# M_E_ext_proto.net
KiCad netlist of a schematic drawn in EAGLE
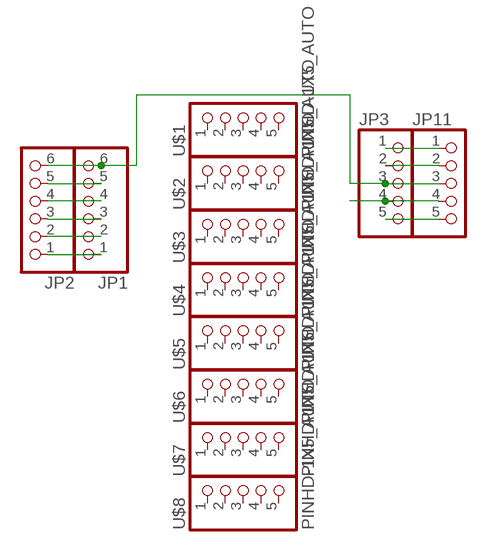
[diagram p0: schematic, sheet 1]

(export (version "E")
  (design (tool "Eeschema 10.0.6"))
  (components
    (comp (ref "JP1")
      (value "PINHD-1X6")
      (footprint "eagle-import:1X06")
      (libsource (lib "eagle-import") (part "PINHD-1X6"))
    )
    (comp (ref "JP2")
      (value "PINHD-1X6")
      (footprint "eagle-import:1X06")
      (libsource (lib "eagle-import") (part "PINHD-1X6"))
    )
    (comp (ref "JP3")
      (value "PINHD-1X5")
      (footprint "eagle-import:1X05")
      (libsource (lib "eagle-import") (part "PINHD-1X5"))
    )
    (comp (ref "JP11")
      (value "PINHD-1X5")
      (footprint "eagle-import:1X05")
      (libsource (lib "eagle-import") (part "PINHD-1X5"))
    )
    (comp (ref "U$1")
      (value "PINHD-1X5_AUTO")
      (footprint "eagle-import:1X5_AUTO")
      (libsource (lib "eagle-import") (part "PINHD-1X5_AUTO"))
    )
    (comp (ref "U$2")
      (value "PINHD-1X5_AUTO")
      (footprint "eagle-import:1X5_AUTO")
      (libsource (lib "eagle-import") (part "PINHD-1X5_AUTO"))
    )
    (comp (ref "U$3")
      (value "PINHD-1X5_AUTO")
      (footprint "eagle-import:1X5_AUTO")
      (libsource (lib "eagle-import") (part "PINHD-1X5_AUTO"))
    )
    (comp (ref "U$4")
      (value "PINHD-1X5_AUTO")
      (footprint "eagle-import:1X5_AUTO")
      (libsource (lib "eagle-import") (part "PINHD-1X5_AUTO"))
    )
    (comp (ref "U$5")
      (value "PINHD-1X5_AUTO")
      (footprint "eagle-import:1X5_AUTO")
      (libsource (lib "eagle-import") (part "PINHD-1X5_AUTO"))
    )
    (comp (ref "U$6")
      (value "PINHD-1X5_AUTO")
      (footprint "eagle-import:1X5_AUTO")
      (libsource (lib "eagle-import") (part "PINHD-1X5_AUTO"))
    )
    (comp (ref "U$7")
      (value "PINHD-1X5_AUTO")
      (footprint "eagle-import:1X5_AUTO")
      (libsource (lib "eagle-import") (part "PINHD-1X5_AUTO"))
    )
    (comp (ref "U$8")
      (value "PINHD-1X5_AUTO")
      (footprint "eagle-import:1X5_AUTO")
      (libsource (lib "eagle-import") (part "PINHD-1X5_AUTO"))
    )
  )
  (nets
    (net (code "1") (name "Net-(JP1-Pad1)") (class "Default")
      (node (ref "JP1") (pin "1") (pinfunction "1_1") (pintype "passive"))
      (node (ref "JP2") (pin "1") (pinfunction "1_1") (pintype "passive"))
    )
    (net (code "2") (name "Net-(JP1-Pad2)") (class "Default")
      (node (ref "JP1") (pin "2") (pinfunction "2_2") (pintype "passive"))
      (node (ref "JP2") (pin "2") (pinfunction "2_2") (pintype "passive"))
    )
    (net (code "3") (name "Net-(JP1-Pad3)") (class "Default")
      (node (ref "JP1") (pin "3") (pinfunction "3_3") (pintype "passive"))
      (node (ref "JP2") (pin "3") (pinfunction "3_3") (pintype "passive"))
    )
    (net (code "4") (name "Net-(JP1-Pad4)") (class "Default")
      (node (ref "JP1") (pin "4") (pinfunction "4_4") (pintype "passive"))
      (node (ref "JP2") (pin "4") (pinfunction "4_4") (pintype "passive"))
    )
    (net (code "5") (name "Net-(JP1-Pad5)") (class "Default")
      (node (ref "JP1") (pin "5") (pinfunction "5_5") (pintype "passive"))
      (node (ref "JP2") (pin "5") (pinfunction "5_5") (pintype "passive"))
    )
    (net (code "6") (name "Net-(JP1-Pad6)") (class "Default")
      (node (ref "JP1") (pin "6") (pinfunction "6_6") (pintype "passive"))
      (node (ref "JP11") (pin "3") (pinfunction "3_3") (pintype "passive"))
      (node (ref "JP2") (pin "6") (pinfunction "6_6") (pintype "passive"))
      (node (ref "JP3") (pin "3") (pinfunction "3_3") (pintype "passive"))
    )
    (net (code "7") (name "Net-(JP11-Pad1)") (class "Default")
      (node (ref "JP11") (pin "1") (pinfunction "1_1") (pintype "passive"))
      (node (ref "JP3") (pin "1") (pinfunction "1_1") (pintype "passive"))
    )
    (net (code "8") (name "Net-(JP11-Pad2)") (class "Default")
      (node (ref "JP11") (pin "2") (pinfunction "2_2") (pintype "passive"))
      (node (ref "JP3") (pin "2") (pinfunction "2_2") (pintype "passive"))
    )
    (net (code "9") (name "Net-(JP11-Pad4)") (class "Default")
      (node (ref "JP11") (pin "4") (pinfunction "4_4") (pintype "passive"))
      (node (ref "JP3") (pin "4") (pinfunction "4_4") (pintype "passive"))
    )
    (net (code "10") (name "Net-(JP11-Pad5)") (class "Default")
      (node (ref "JP11") (pin "5") (pinfunction "5_5") (pintype "passive"))
      (node (ref "JP3") (pin "5") (pinfunction "5_5") (pintype "passive"))
    )
    (net (code "11") (name "unconnected-(U$1-Pad1)") (class "Default")
      (node (ref "U$1") (pin "1") (pinfunction "1_1") (pintype "passive"))
    )
    (net (code "12") (name "unconnected-(U$1-Pad2)") (class "Default")
      (node (ref "U$1") (pin "2") (pinfunction "2_2") (pintype "passive"))
    )
    (net (code "13") (name "unconnected-(U$1-Pad3)") (class "Default")
      (node (ref "U$1") (pin "3") (pinfunction "3_3") (pintype "passive"))
    )
    (net (code "14") (name "unconnected-(U$1-Pad4)") (class "Default")
      (node (ref "U$1") (pin "4") (pinfunction "4_4") (pintype "passive"))
    )
    (net (code "15") (name "unconnected-(U$1-Pad5)") (class "Default")
      (node (ref "U$1") (pin "5") (pinfunction "5_5") (pintype "passive"))
    )
    (net (code "16") (name "unconnected-(U$2-Pad1)") (class "Default")
      (node (ref "U$2") (pin "1") (pinfunction "1_1") (pintype "passive"))
    )
    (net (code "17") (name "unconnected-(U$2-Pad2)") (class "Default")
      (node (ref "U$2") (pin "2") (pinfunction "2_2") (pintype "passive"))
    )
    (net (code "18") (name "unconnected-(U$2-Pad3)") (class "Default")
      (node (ref "U$2") (pin "3") (pinfunction "3_3") (pintype "passive"))
    )
    (net (code "19") (name "unconnected-(U$2-Pad4)") (class "Default")
      (node (ref "U$2") (pin "4") (pinfunction "4_4") (pintype "passive"))
    )
    (net (code "20") (name "unconnected-(U$2-Pad5)") (class "Default")
      (node (ref "U$2") (pin "5") (pinfunction "5_5") (pintype "passive"))
    )
    (net (code "21") (name "unconnected-(U$3-Pad1)") (class "Default")
      (node (ref "U$3") (pin "1") (pinfunction "1_1") (pintype "passive"))
    )
    (net (code "22") (name "unconnected-(U$3-Pad2)") (class "Default")
      (node (ref "U$3") (pin "2") (pinfunction "2_2") (pintype "passive"))
    )
    (net (code "23") (name "unconnected-(U$3-Pad3)") (class "Default")
      (node (ref "U$3") (pin "3") (pinfunction "3_3") (pintype "passive"))
    )
    (net (code "24") (name "unconnected-(U$3-Pad4)") (class "Default")
      (node (ref "U$3") (pin "4") (pinfunction "4_4") (pintype "passive"))
    )
    (net (code "25") (name "unconnected-(U$3-Pad5)") (class "Default")
      (node (ref "U$3") (pin "5") (pinfunction "5_5") (pintype "passive"))
    )
    (net (code "26") (name "unconnected-(U$4-Pad1)") (class "Default")
      (node (ref "U$4") (pin "1") (pinfunction "1_1") (pintype "passive"))
    )
    (net (code "27") (name "unconnected-(U$4-Pad2)") (class "Default")
      (node (ref "U$4") (pin "2") (pinfunction "2_2") (pintype "passive"))
    )
    (net (code "28") (name "unconnected-(U$4-Pad3)") (class "Default")
      (node (ref "U$4") (pin "3") (pinfunction "3_3") (pintype "passive"))
    )
    (net (code "29") (name "unconnected-(U$4-Pad4)") (class "Default")
      (node (ref "U$4") (pin "4") (pinfunction "4_4") (pintype "passive"))
    )
    (net (code "30") (name "unconnected-(U$4-Pad5)") (class "Default")
      (node (ref "U$4") (pin "5") (pinfunction "5_5") (pintype "passive"))
    )
    (net (code "31") (name "unconnected-(U$5-Pad1)") (class "Default")
      (node (ref "U$5") (pin "1") (pinfunction "1_1") (pintype "passive"))
    )
    (net (code "32") (name "unconnected-(U$5-Pad2)") (class "Default")
      (node (ref "U$5") (pin "2") (pinfunction "2_2") (pintype "passive"))
    )
    (net (code "33") (name "unconnected-(U$5-Pad3)") (class "Default")
      (node (ref "U$5") (pin "3") (pinfunction "3_3") (pintype "passive"))
    )
    (net (code "34") (name "unconnected-(U$5-Pad4)") (class "Default")
      (node (ref "U$5") (pin "4") (pinfunction "4_4") (pintype "passive"))
    )
    (net (code "35") (name "unconnected-(U$5-Pad5)") (class "Default")
      (node (ref "U$5") (pin "5") (pinfunction "5_5") (pintype "passive"))
    )
    (net (code "36") (name "unconnected-(U$6-Pad1)") (class "Default")
      (node (ref "U$6") (pin "1") (pinfunction "1_1") (pintype "passive"))
    )
    (net (code "37") (name "unconnected-(U$6-Pad2)") (class "Default")
      (node (ref "U$6") (pin "2") (pinfunction "2_2") (pintype "passive"))
    )
    (net (code "38") (name "unconnected-(U$6-Pad3)") (class "Default")
      (node (ref "U$6") (pin "3") (pinfunction "3_3") (pintype "passive"))
    )
    (net (code "39") (name "unconnected-(U$6-Pad4)") (class "Default")
      (node (ref "U$6") (pin "4") (pinfunction "4_4") (pintype "passive"))
    )
    (net (code "40") (name "unconnected-(U$6-Pad5)") (class "Default")
      (node (ref "U$6") (pin "5") (pinfunction "5_5") (pintype "passive"))
    )
    (net (code "41") (name "unconnected-(U$7-Pad1)") (class "Default")
      (node (ref "U$7") (pin "1") (pinfunction "1_1") (pintype "passive"))
    )
    (net (code "42") (name "unconnected-(U$7-Pad2)") (class "Default")
      (node (ref "U$7") (pin "2") (pinfunction "2_2") (pintype "passive"))
    )
    (net (code "43") (name "unconnected-(U$7-Pad3)") (class "Default")
      (node (ref "U$7") (pin "3") (pinfunction "3_3") (pintype "passive"))
    )
    (net (code "44") (name "unconnected-(U$7-Pad4)") (class "Default")
      (node (ref "U$7") (pin "4") (pinfunction "4_4") (pintype "passive"))
    )
    (net (code "45") (name "unconnected-(U$7-Pad5)") (class "Default")
      (node (ref "U$7") (pin "5") (pinfunction "5_5") (pintype "passive"))
    )
    (net (code "46") (name "unconnected-(U$8-Pad1)") (class "Default")
      (node (ref "U$8") (pin "1") (pinfunction "1_1") (pintype "passive"))
    )
    (net (code "47") (name "unconnected-(U$8-Pad2)") (class "Default")
      (node (ref "U$8") (pin "2") (pinfunction "2_2") (pintype "passive"))
    )
    (net (code "48") (name "unconnected-(U$8-Pad3)") (class "Default")
      (node (ref "U$8") (pin "3") (pinfunction "3_3") (pintype "passive"))
    )
    (net (code "49") (name "unconnected-(U$8-Pad4)") (class "Default")
      (node (ref "U$8") (pin "4") (pinfunction "4_4") (pintype "passive"))
    )
    (net (code "50") (name "unconnected-(U$8-Pad5)") (class "Default")
      (node (ref "U$8") (pin "5") (pinfunction "5_5") (pintype "passive"))
    )
  )
)
